# POWER.net
KiCad netlist of a schematic drawn in Altium Designer
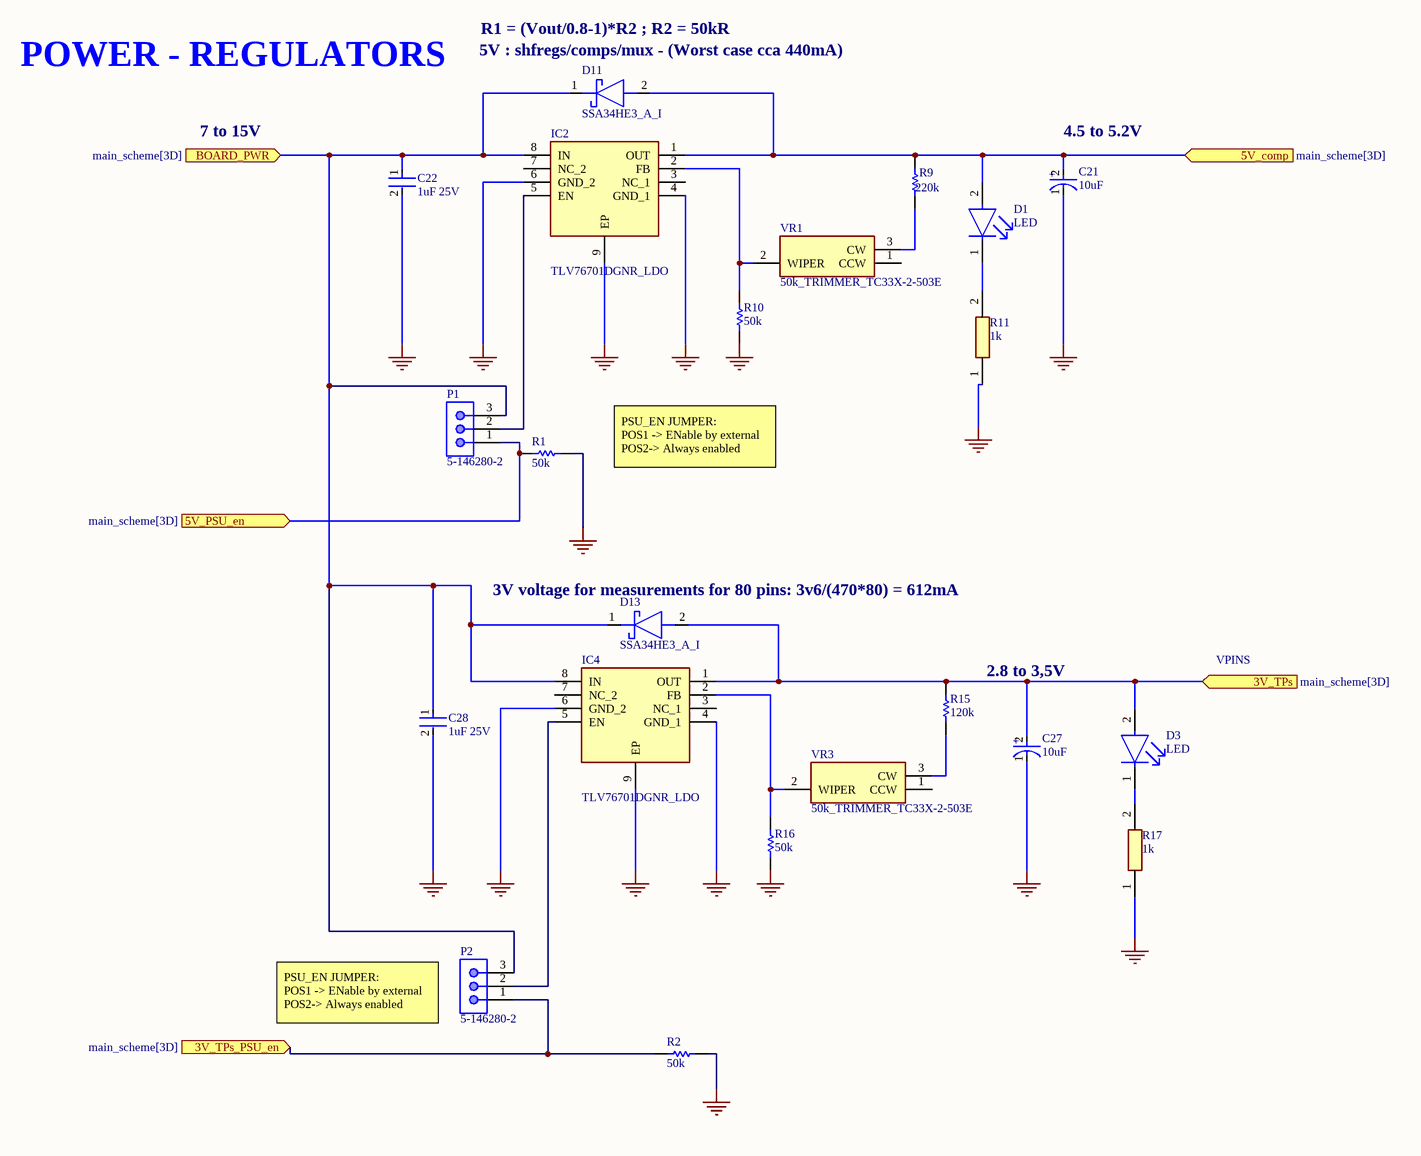
[diagram p0: POWER.SchDoc]

(export (version "E")
  (design (tool "Eeschema 10.0.6"))
  (components
    (comp (ref "C21")
      (value "10uF")
      (footprint "PcbLib1:0603_tantal")
      (description "CAP TANT POLY 10UF 10V SMD")
      (fields
        (field (name "MANUFACTURER PART NUMBER") "F381A106MMAAH1")
        (field (name "OCTOPART") "https://octopart.com/f381a106mmaah1-avx-67040376")
      )
      (libsource (lib "Schlib1") (part "0603 TantalCAP"))
    )
    (comp (ref "C22")
      (value "1uF 25V")
      (footprint "PcbLib1:0603-CAP")
      (description "General Purpose Ceramic Capacitor, 0603, 1uF, 10%, X5R, 15%, 25V")
      (fields (field (name "VOLTAGE") "25V") (field (name "TOLERANCE") "20%"))
      (libsource (lib "Schlib1") (part "0603-CAP"))
    )
    (comp (ref "C27")
      (value "10uF")
      (footprint "PcbLib1:0603_tantal")
      (description "CAP TANT POLY 10UF 10V SMD")
      (fields
        (field (name "MANUFACTURER PART NUMBER") "F381A106MMAAH1")
        (field (name "OCTOPART") "https://octopart.com/f381a106mmaah1-avx-67040376")
      )
      (libsource (lib "Schlib1") (part "0603 TantalCAP"))
    )
    (comp (ref "C28")
      (value "1uF 25V")
      (footprint "PcbLib1:0603-CAP")
      (description "General Purpose Ceramic Capacitor, 0603, 1uF, 10%, X5R, 15%, 25V")
      (fields (field (name "VOLTAGE") "25V") (field (name "TOLERANCE") "20%"))
      (libsource (lib "Schlib1") (part "0603-CAP"))
    )
    (comp (ref "D1")
      (value "LED")
      (footprint "PcbLib1:0603_RED_LED")
      (description "LED RED DIFFUSED 1608 SMD")
      (fields
        (field (name "MANUFACTURER") "Rohm")
        (field (name "OCTOPART") "https://octopart.com/sml-d12u1wt86-rohm-70850259")
      )
      (libsource (lib "Schlib1") (part "0603_RED_LED_2V2"))
    )
    (comp (ref "D3")
      (value "LED")
      (footprint "PcbLib1:0603_RED_LED")
      (description "LED RED DIFFUSED 1608 SMD")
      (fields
        (field (name "MANUFACTURER") "Rohm")
        (field (name "OCTOPART") "https://octopart.com/sml-d12u1wt86-rohm-70850259")
      )
      (libsource (lib "Schlib1") (part "0603_RED_LED_2V2"))
    )
    (comp (ref "D11")
      (value "SSA34HE3_A_I")
      (footprint "SamacSys:DIONM5127X229N")
      (description "Schottky Diode")
      (fields
        (field (name "MANUFACTURER_PART_NUMBER") "SSA34HE3_A/I")
        (field (name "MOUSER PART NUMBER") "78-SSA34HE3_A/I")
      )
      (libsource (lib "*") (part "SSA34HE3_A_I"))
    )
    (comp (ref "D13")
      (value "SSA34HE3_A_I")
      (footprint "SamacSys:DIONM5127X229N")
      (description "Schottky Diode")
      (fields
        (field (name "MANUFACTURER_PART_NUMBER") "SSA34HE3_A/I")
        (field (name "MOUSER PART NUMBER") "78-SSA34HE3_A/I")
      )
      (libsource (lib "*") (part "SSA34HE3_A_I"))
    )
    (comp (ref "IC2")
      (value "TLV76701DGNR_LDO")
      (footprint "PcbLib1:SOP65P490X110-9N")
      (description "Integrated Circuit")
      (fields (field (name "MANUFACTURER_PART_NUMBER") "TLV76701DGNR"))
      (libsource (lib "Schlib1") (part "TLV76701DGNR_LDO"))
    )
    (comp (ref "IC4")
      (value "TLV76701DGNR_LDO")
      (footprint "PcbLib1:SOP65P490X110-9N")
      (description "Integrated Circuit")
      (fields (field (name "MANUFACTURER_PART_NUMBER") "TLV76701DGNR"))
      (libsource (lib "Schlib1") (part "TLV76701DGNR_LDO"))
    )
    (comp (ref "P1")
      (value "5-146280-2")
      (footprint "2.54mm header 3x1")
      (fields (field (name "MANUFACTURER") "TE Connectivity"))
      (libsource (lib "Schlib1") (part "3x1 Header"))
    )
    (comp (ref "P2")
      (value "5-146280-2")
      (footprint "2.54mm header 3x1")
      (fields (field (name "MANUFACTURER") "TE Connectivity"))
      (libsource (lib "Schlib1") (part "3x1 Header"))
    )
    (comp (ref "R1")
      (value "50k")
      (footprint "PcbLib1:RESC1005X40X25NL05T05")
      (fields (field (name "PART NUMBER") "ERJ2RKF6800X") (field (name "MANUFACTURER") "Panasonic"))
      (libsource (lib "Schlib1") (part "Resistor 0402 100mW"))
    )
    (comp (ref "R2")
      (value "50k")
      (footprint "PcbLib1:RESC1005X40X25NL05T05")
      (fields (field (name "PART NUMBER") "ERJ2RKF6800X") (field (name "MANUFACTURER") "Panasonic"))
      (libsource (lib "Schlib1") (part "Resistor 0402 100mW"))
    )
    (comp (ref "R9")
      (value "220k")
      (footprint "PcbLib1:RESC1005X40X25NL05T05")
      (fields (field (name "PART NUMBER") "ERJ2RKF6800X") (field (name "MANUFACTURER") "Panasonic"))
      (libsource (lib "Schlib1") (part "Resistor 0402 100mW"))
    )
    (comp (ref "R10")
      (value "50k")
      (footprint "PcbLib1:RESC1005X40X25NL05T05")
      (fields (field (name "PART NUMBER") "ERJ2RKF6800X") (field (name "MANUFACTURER") "Panasonic"))
      (libsource (lib "Schlib1") (part "Resistor 0402 100mW"))
    )
    (comp (ref "R11")
      (value "1k")
      (footprint "PcbLib1:0603- SMD resistor")
      (description "Resistor")
      (fields
        (field (name "MANUFACTURER_PART_NUMBER") "CR0603-J/-9R1ELF")
        (field (name "MOUSER PART NUMBER") "652-CR0603-J/-9R1ELF")
      )
      (libsource (lib "Schlib1") (part "0603 - SMD RESISTOR"))
    )
    (comp (ref "R15")
      (value "120k")
      (footprint "PcbLib1:RESC1005X40X25NL05T05")
      (fields (field (name "PART NUMBER") "ERJ2RKF6800X") (field (name "MANUFACTURER") "Panasonic"))
      (libsource (lib "Schlib1") (part "Resistor 0402 100mW"))
    )
    (comp (ref "R16")
      (value "50k")
      (footprint "PcbLib1:RESC1005X40X25NL05T05")
      (fields (field (name "PART NUMBER") "ERJ2RKF6800X") (field (name "MANUFACTURER") "Panasonic"))
      (libsource (lib "Schlib1") (part "Resistor 0402 100mW"))
    )
    (comp (ref "R17")
      (value "1k")
      (footprint "PcbLib1:0603- SMD resistor")
      (description "Resistor")
      (fields
        (field (name "MANUFACTURER_PART_NUMBER") "CR0603-J/-9R1ELF")
        (field (name "MOUSER PART NUMBER") "652-CR0603-J/-9R1ELF")
      )
      (libsource (lib "Schlib1") (part "0603 - SMD RESISTOR"))
    )
    (comp (ref "VR1")
      (value "50k_TRIMMER_TC33X-2-503E")
      (footprint "PcbLib1:TC33X2503E")
      (description "Variable Resistor")
      (fields
        (field (name "MANUFACTURER_PART_NUMBER") "TC33X-2-503E")
        (field (name "MOUSER PART NUMBER") "652-TC33X-2-503E")
      )
      (libsource (lib "Schlib1") (part "50k_TRIMMER_TC33X-2-503E"))
    )
    (comp (ref "VR3")
      (value "50k_TRIMMER_TC33X-2-503E")
      (footprint "PcbLib1:TC33X2503E")
      (description "Variable Resistor")
      (fields
        (field (name "MANUFACTURER_PART_NUMBER") "TC33X-2-503E")
        (field (name "MOUSER PART NUMBER") "652-TC33X-2-503E")
      )
      (libsource (lib "Schlib1") (part "50k_TRIMMER_TC33X-2-503E"))
    )
  )
  (nets
    (net (code "1") (name "/3V_TPs") (class "Default")
      (node (ref "C27") (pin "2") (pinfunction "A_2") (pintype "passive"))
      (node (ref "D13") (pin "2") (pinfunction "A_2") (pintype "passive"))
      (node (ref "D3") (pin "2") (pinfunction "A_2") (pintype "passive"))
      (node (ref "IC4") (pin "1") (pinfunction "OUT_1") (pintype "passive"))
      (node (ref "R15") (pin "1") (pinfunction "1_1") (pintype "passive"))
    )
    (net (code "2") (name "/3V_TPs_PSU_en") (class "Default")
      (node (ref "P2") (pin "1") (pinfunction "1_1") (pintype "passive"))
      (node (ref "R2") (pin "2") (pinfunction "2_2") (pintype "passive"))
    )
    (net (code "3") (name "/5V_PSU_en") (class "Default")
      (node (ref "P1") (pin "1") (pinfunction "1_1") (pintype "passive"))
      (node (ref "R1") (pin "2") (pinfunction "2_2") (pintype "passive"))
    )
    (net (code "4") (name "/5V_comp") (class "Default")
      (node (ref "C21") (pin "2") (pinfunction "A_2") (pintype "passive"))
      (node (ref "D1") (pin "2") (pinfunction "A_2") (pintype "passive"))
      (node (ref "D11") (pin "2") (pinfunction "A_2") (pintype "passive"))
      (node (ref "IC2") (pin "1") (pinfunction "OUT_1") (pintype "passive"))
      (node (ref "R9") (pin "1") (pinfunction "1_1") (pintype "passive"))
    )
    (net (code "5") (name "/BOARD_PWR") (class "Default")
      (node (ref "C22") (pin "1") (pinfunction "1_1") (pintype "passive"))
      (node (ref "C28") (pin "1") (pinfunction "1_1") (pintype "passive"))
      (node (ref "D11") (pin "1") (pinfunction "K_1") (pintype "passive"))
      (node (ref "D13") (pin "1") (pinfunction "K_1") (pintype "passive"))
      (node (ref "IC2") (pin "8") (pinfunction "IN_8") (pintype "passive"))
      (node (ref "IC4") (pin "8") (pinfunction "IN_8") (pintype "passive"))
      (node (ref "P1") (pin "3") (pinfunction "3_3") (pintype "passive"))
      (node (ref "P2") (pin "3") (pinfunction "3_3") (pintype "passive"))
    )
    (net (code "6") (name "GND") (class "Default")
      (node (ref "C21") (pin "1") (pinfunction "C_1") (pintype "passive"))
      (node (ref "C22") (pin "2") (pinfunction "2_2") (pintype "passive"))
      (node (ref "C27") (pin "1") (pinfunction "C_1") (pintype "passive"))
      (node (ref "C28") (pin "2") (pinfunction "2_2") (pintype "passive"))
      (node (ref "IC2") (pin "4") (pinfunction "GND_1_4") (pintype "passive"))
      (node (ref "IC2") (pin "6") (pinfunction "GND_2_6") (pintype "passive"))
      (node (ref "IC2") (pin "9") (pinfunction "EP_9") (pintype "passive"))
      (node (ref "IC4") (pin "4") (pinfunction "GND_1_4") (pintype "passive"))
      (node (ref "IC4") (pin "6") (pinfunction "GND_2_6") (pintype "passive"))
      (node (ref "IC4") (pin "9") (pinfunction "EP_9") (pintype "passive"))
      (node (ref "R1") (pin "1") (pinfunction "1_1") (pintype "passive"))
      (node (ref "R10") (pin "2") (pinfunction "2_2") (pintype "passive"))
      (node (ref "R11") (pin "1") (pinfunction "1_1") (pintype "passive"))
      (node (ref "R16") (pin "2") (pinfunction "2_2") (pintype "passive"))
      (node (ref "R17") (pin "1") (pinfunction "1_1") (pintype "passive"))
      (node (ref "R2") (pin "1") (pinfunction "1_1") (pintype "passive"))
    )
    (net (code "7") (name "Net-(D1-C)") (class "Default")
      (node (ref "D1") (pin "1") (pinfunction "C_1") (pintype "passive"))
      (node (ref "R11") (pin "2") (pinfunction "2_2") (pintype "passive"))
    )
    (net (code "8") (name "Net-(D3-C)") (class "Default")
      (node (ref "D3") (pin "1") (pinfunction "C_1") (pintype "passive"))
      (node (ref "R17") (pin "2") (pinfunction "2_2") (pintype "passive"))
    )
    (net (code "9") (name "Net-(IC2-EN)") (class "Default")
      (node (ref "IC2") (pin "5") (pinfunction "EN_5") (pintype "passive"))
      (node (ref "P1") (pin "2") (pinfunction "2_2") (pintype "passive"))
    )
    (net (code "10") (name "Net-(IC2-FB)") (class "Default")
      (node (ref "IC2") (pin "2") (pinfunction "FB_2") (pintype "passive"))
      (node (ref "R10") (pin "1") (pinfunction "1_1") (pintype "passive"))
      (node (ref "VR1") (pin "2") (pinfunction "WIPER_2") (pintype "passive"))
    )
    (net (code "11") (name "Net-(IC4-EN)") (class "Default")
      (node (ref "IC4") (pin "5") (pinfunction "EN_5") (pintype "passive"))
      (node (ref "P2") (pin "2") (pinfunction "2_2") (pintype "passive"))
    )
    (net (code "12") (name "Net-(IC4-FB)") (class "Default")
      (node (ref "IC4") (pin "2") (pinfunction "FB_2") (pintype "passive"))
      (node (ref "R16") (pin "1") (pinfunction "1_1") (pintype "passive"))
      (node (ref "VR3") (pin "2") (pinfunction "WIPER_2") (pintype "passive"))
    )
    (net (code "13") (name "Net-(VR1-CW)") (class "Default")
      (node (ref "R9") (pin "2") (pinfunction "2_2") (pintype "passive"))
      (node (ref "VR1") (pin "3") (pinfunction "CW_3") (pintype "passive"))
    )
    (net (code "14") (name "Net-(VR3-CW)") (class "Default")
      (node (ref "R15") (pin "2") (pinfunction "2_2") (pintype "passive"))
      (node (ref "VR3") (pin "3") (pinfunction "CW_3") (pintype "passive"))
    )
    (net (code "15") (name "unconnected-(IC2-NC_1-Pad3)") (class "Default")
      (node (ref "IC2") (pin "3") (pinfunction "NC_1_3") (pintype "passive"))
    )
    (net (code "16") (name "unconnected-(IC2-NC_2-Pad7)") (class "Default")
      (node (ref "IC2") (pin "7") (pinfunction "NC_2_7") (pintype "passive"))
    )
    (net (code "17") (name "unconnected-(IC4-NC_1-Pad3)") (class "Default")
      (node (ref "IC4") (pin "3") (pinfunction "NC_1_3") (pintype "passive"))
    )
    (net (code "18") (name "unconnected-(IC4-NC_2-Pad7)") (class "Default")
      (node (ref "IC4") (pin "7") (pinfunction "NC_2_7") (pintype "passive"))
    )
    (net (code "19") (name "unconnected-(VR1-CCW-Pad1)") (class "Default")
      (node (ref "VR1") (pin "1") (pinfunction "CCW_1") (pintype "passive"))
    )
    (net (code "20") (name "unconnected-(VR3-CCW-Pad1)") (class "Default")
      (node (ref "VR3") (pin "1") (pinfunction "CCW_1") (pintype "passive"))
    )
  )
)
